# Flip-Flop.net
KiCad netlist of a schematic drawn in EAGLE
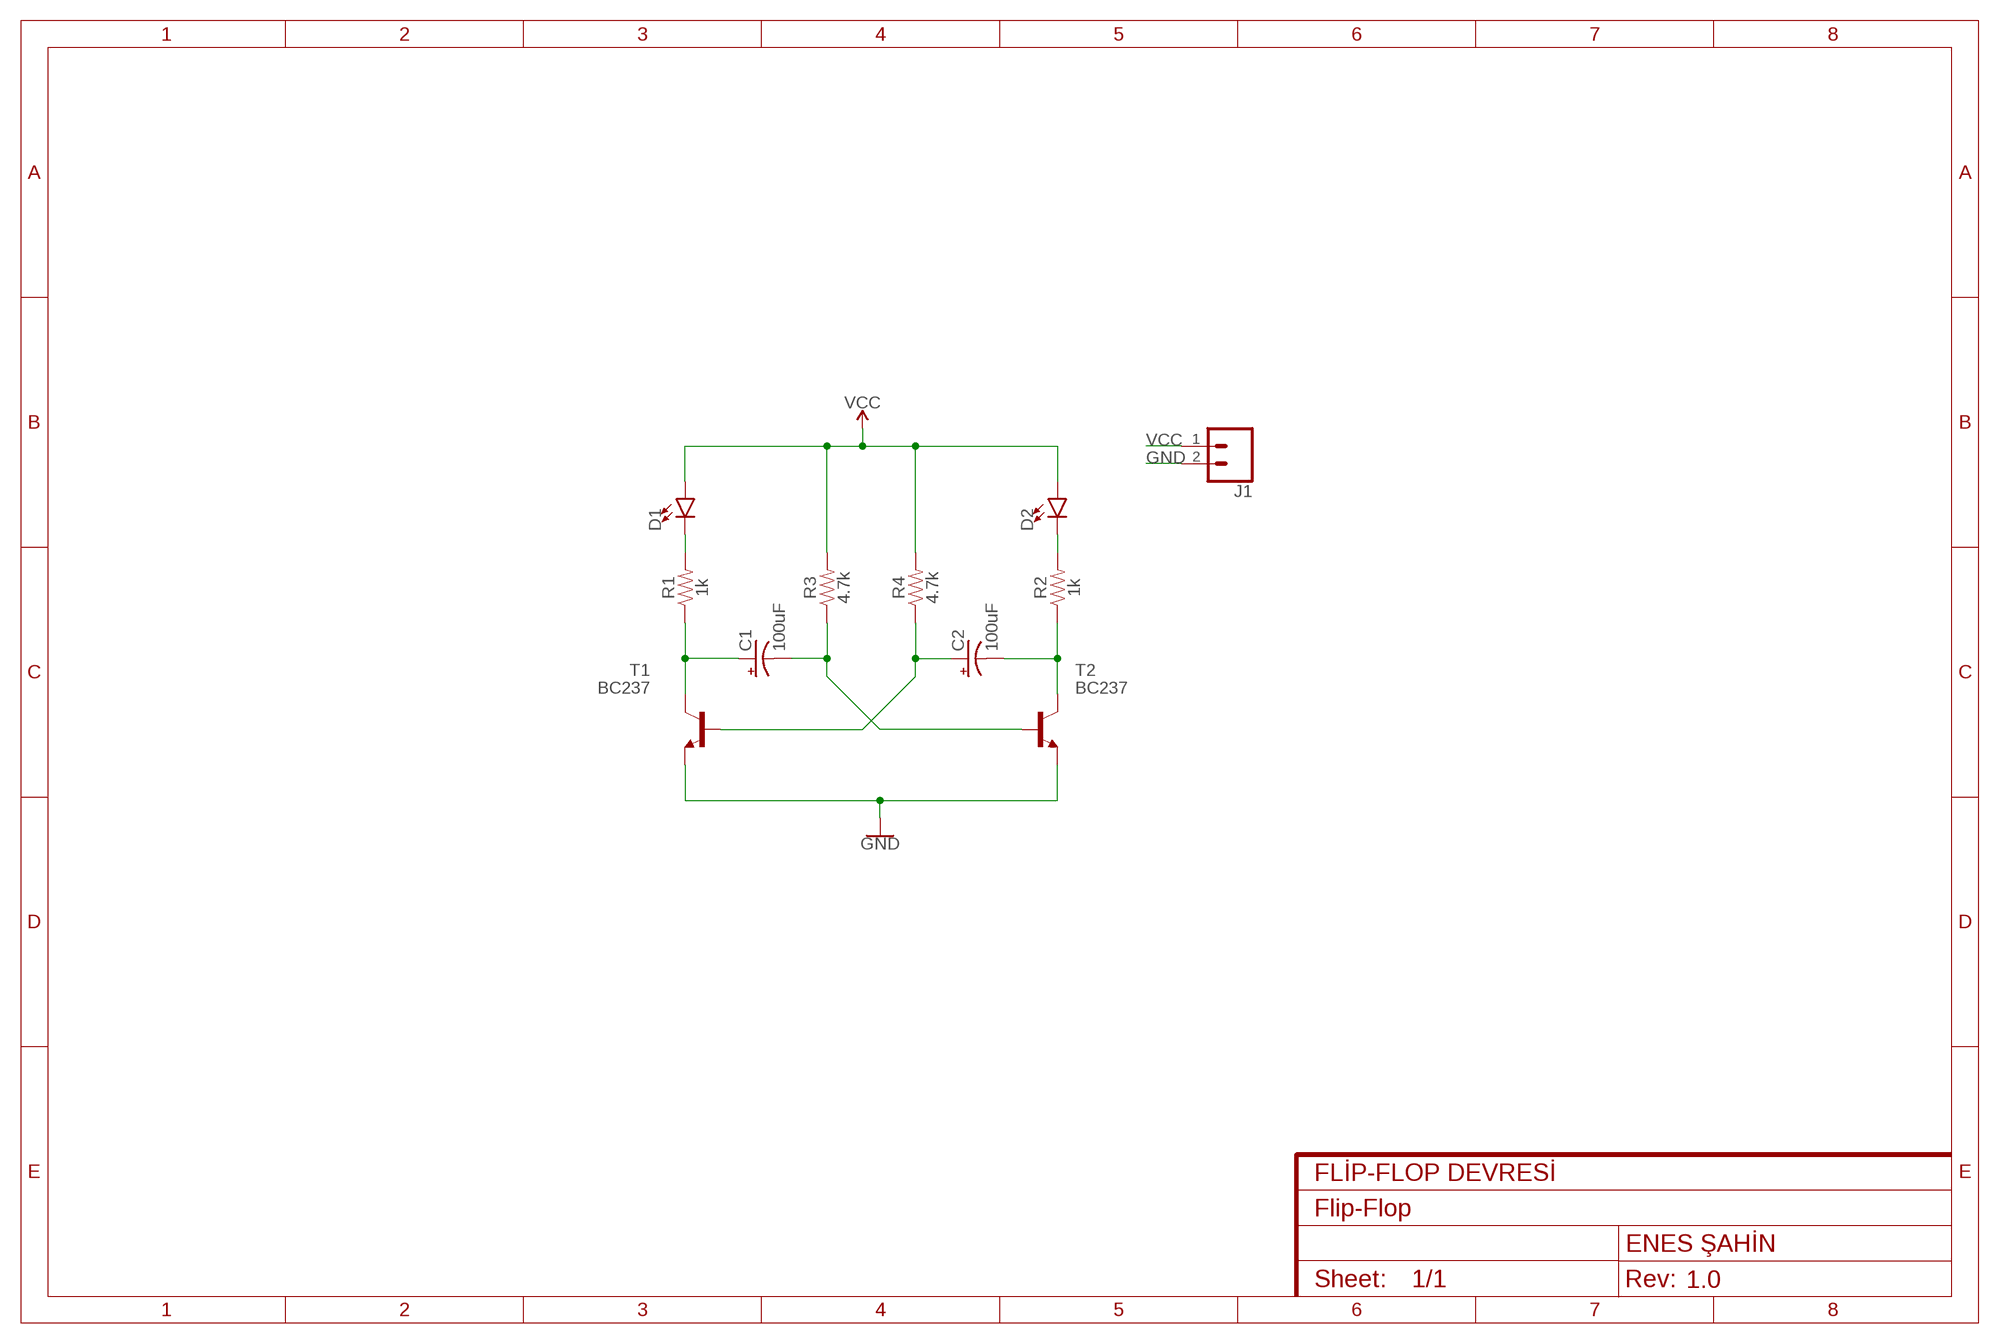
[diagram p0: schematic, sheet 1]

(export (version "E")
  (design (tool "Eeschema 10.0.6"))
  (components
    (comp (ref "C1")
      (value "100uF")
      (footprint "eagle-import:CPOL-RADIAL-2.5MM-6.5MM")
      (libsource (lib "eagle-import") (part "100UF-POLAR-RADIAL-2.5MM-25V-20%"))
    )
    (comp (ref "C2")
      (value "100uF")
      (footprint "eagle-import:CPOL-RADIAL-2.5MM-6.5MM")
      (libsource (lib "eagle-import") (part "100UF-POLAR-RADIAL-2.5MM-25V-20%"))
    )
    (comp (ref "D1")
      (value "LED-3MM-NO_SILK")
      (footprint "eagle-import:LED_3MM-NS")
      (libsource (lib "eagle-import") (part "LED-3MM-NO_SILK"))
    )
    (comp (ref "D2")
      (value "LED-3MM-NO_SILK")
      (footprint "eagle-import:LED_3MM-NS")
      (libsource (lib "eagle-import") (part "LED-3MM-NO_SILK"))
    )
    (comp (ref "J1")
      (value "CONN_02")
      (footprint "eagle-import:1X02")
      (libsource (lib "eagle-import") (part "CONN_02"))
    )
    (comp (ref "R1")
      (value "1k")
      (footprint "eagle-import:AXIAL-0.3")
      (libsource (lib "eagle-import") (part "1KOHM-HORIZ-1/4W-1%"))
    )
    (comp (ref "R2")
      (value "1k")
      (footprint "eagle-import:AXIAL-0.3")
      (libsource (lib "eagle-import") (part "1KOHM-HORIZ-1/4W-1%"))
    )
    (comp (ref "R3")
      (value "4.7k")
      (footprint "eagle-import:AXIAL-0.3")
      (libsource (lib "eagle-import") (part "1KOHM-HORIZ-1/4W-1%"))
    )
    (comp (ref "R4")
      (value "4.7k")
      (footprint "eagle-import:AXIAL-0.3")
      (libsource (lib "eagle-import") (part "1KOHM-HORIZ-1/4W-1%"))
    )
    (comp (ref "T1")
      (value "BC237")
      (footprint "eagle-import:TO92")
      (libsource (lib "eagle-import") (part "BC237"))
    )
    (comp (ref "T2")
      (value "BC237")
      (footprint "eagle-import:TO92")
      (libsource (lib "eagle-import") (part "BC237"))
    )
  )
  (nets
    (net (code "1") (name "GND") (class "Default")
      (node (ref "J1") (pin "2") (pinfunction "2_2") (pintype "passive"))
      (node (ref "T1") (pin "1") (pinfunction "E_1") (pintype "passive"))
      (node (ref "T2") (pin "1") (pinfunction "E_1") (pintype "passive"))
    )
    (net (code "2") (name "Net-(C1-+)") (class "Default")
      (node (ref "C1") (pin "1") (pinfunction "+_1") (pintype "passive"))
      (node (ref "R1") (pin "P$1") (pinfunction "1_P$1") (pintype "passive"))
      (node (ref "T1") (pin "3") (pinfunction "C_3") (pintype "passive"))
    )
    (net (code "3") (name "Net-(C1--)") (class "Default")
      (node (ref "C1") (pin "2") (pinfunction "-_2") (pintype "passive"))
      (node (ref "R3") (pin "P$1") (pinfunction "1_P$1") (pintype "passive"))
      (node (ref "T2") (pin "2") (pinfunction "B_2") (pintype "passive"))
    )
    (net (code "4") (name "Net-(C2-+)") (class "Default")
      (node (ref "C2") (pin "1") (pinfunction "+_1") (pintype "passive"))
      (node (ref "R4") (pin "P$1") (pinfunction "1_P$1") (pintype "passive"))
      (node (ref "T1") (pin "2") (pinfunction "B_2") (pintype "passive"))
    )
    (net (code "5") (name "Net-(C2--)") (class "Default")
      (node (ref "C2") (pin "2") (pinfunction "-_2") (pintype "passive"))
      (node (ref "R2") (pin "P$1") (pinfunction "1_P$1") (pintype "passive"))
      (node (ref "T2") (pin "3") (pinfunction "C_3") (pintype "passive"))
    )
    (net (code "6") (name "Net-(D1-C)") (class "Default")
      (node (ref "D1") (pin "K") (pinfunction "C_K") (pintype "passive"))
      (node (ref "R1") (pin "P$2") (pinfunction "2_P$2") (pintype "passive"))
    )
    (net (code "7") (name "Net-(D2-C)") (class "Default")
      (node (ref "D2") (pin "K") (pinfunction "C_K") (pintype "passive"))
      (node (ref "R2") (pin "P$2") (pinfunction "2_P$2") (pintype "passive"))
    )
    (net (code "8") (name "VCC") (class "Default")
      (node (ref "D1") (pin "A") (pinfunction "A_A") (pintype "passive"))
      (node (ref "D2") (pin "A") (pinfunction "A_A") (pintype "passive"))
      (node (ref "J1") (pin "1") (pinfunction "1_1") (pintype "passive"))
      (node (ref "R3") (pin "P$2") (pinfunction "2_P$2") (pintype "passive"))
      (node (ref "R4") (pin "P$2") (pinfunction "2_P$2") (pintype "passive"))
    )
  )
)
